# jn5189_pcb_v1.net
KiCad netlist of a schematic drawn in EAGLE
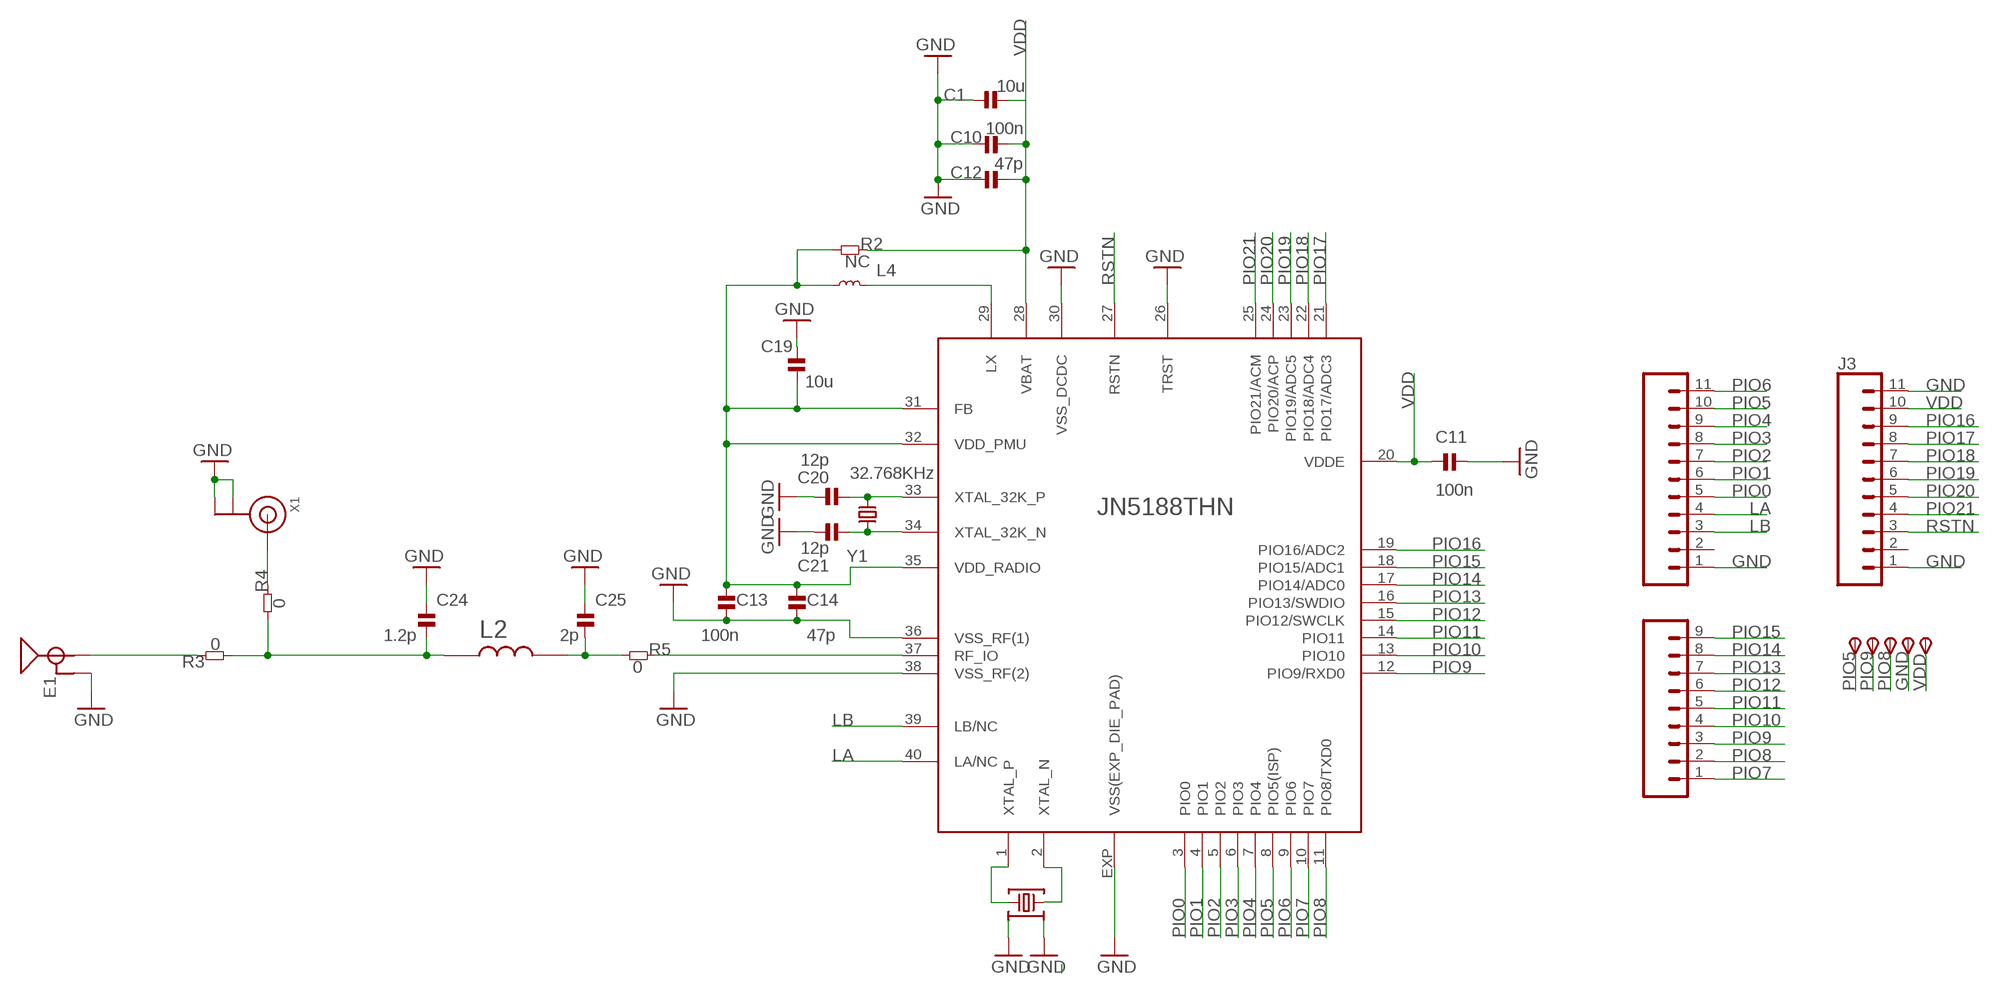
[diagram p0: schematic, sheet 1]

(export (version "E")
  (design (tool "Eeschema 10.0.6"))
  (components
    (comp (ref "3V3")
      (value "TPSTP11R")
      (footprint "eagle-import:TP11R")
      (libsource (lib "eagle-import") (part "TPSTP11R"))
    )
    (comp (ref "C1")
      (value "10u")
      (footprint "eagle-import:_PKG_C_0805")
      (libsource (lib "eagle-import") (part "CAP-0805"))
    )
    (comp (ref "C10")
      (value "100n")
      (footprint "eagle-import:_PKG_C_0402")
      (libsource (lib "eagle-import") (part "CAP-0402"))
    )
    (comp (ref "C11")
      (value "100n")
      (footprint "eagle-import:_PKG_C_0402")
      (libsource (lib "eagle-import") (part "CAP-0402"))
    )
    (comp (ref "C12")
      (value "47p")
      (footprint "eagle-import:_PKG_C_0402")
      (libsource (lib "eagle-import") (part "CAP-0402"))
    )
    (comp (ref "C13")
      (value "100n")
      (footprint "eagle-import:_PKG_C_0402")
      (libsource (lib "eagle-import") (part "CAP-0402"))
    )
    (comp (ref "C14")
      (value "47p")
      (footprint "eagle-import:_PKG_C_0402")
      (libsource (lib "eagle-import") (part "CAP-0402"))
    )
    (comp (ref "C19")
      (value "10u")
      (footprint "eagle-import:_PKG_C_0805")
      (libsource (lib "eagle-import") (part "CAP-0805"))
    )
    (comp (ref "C20")
      (value "12p")
      (footprint "eagle-import:_PKG_C_0402")
      (libsource (lib "eagle-import") (part "CAP-0402"))
    )
    (comp (ref "C21")
      (value "12p")
      (footprint "eagle-import:_PKG_C_0402")
      (libsource (lib "eagle-import") (part "CAP-0402"))
    )
    (comp (ref "C24")
      (value "1.2p")
      (footprint "eagle-import:_PKG_C_0402")
      (libsource (lib "eagle-import") (part "CAP-0402"))
    )
    (comp (ref "C25")
      (value "2p")
      (footprint "eagle-import:_PKG_C_0402")
      (libsource (lib "eagle-import") (part "CAP-0402"))
    )
    (comp (ref "E1")
      (value "ANTENNA-GROUNDEDTRACE-15.2MM")
      (footprint "eagle-import:TRACE_ANTENNA_2.4GHZ_15.2MM")
      (libsource (lib "eagle-import") (part "ANTENNA-GROUNDEDTRACE-15.2MM"))
    )
    (comp (ref "GND")
      (value "TPSTP11R")
      (footprint "eagle-import:TP11R")
      (libsource (lib "eagle-import") (part "TPSTP11R"))
    )
    (comp (ref "ISP")
      (value "TPSTP11R")
      (footprint "eagle-import:TP11R")
      (libsource (lib "eagle-import") (part "TPSTP11R"))
    )
    (comp (ref "J1")
      (value "CONN_11_1.27MM")
      (footprint "eagle-import:1X11-1.27MM")
      (libsource (lib "eagle-import") (part "CONN_11_1.27MM"))
    )
    (comp (ref "J2")
      (value "CONN_051.27MM")
      (footprint "eagle-import:1X05_1.27MM")
      (libsource (lib "eagle-import") (part "CONN_051.27MM"))
    )
    (comp (ref "J3")
      (value "CONN_11_1.27MM")
      (footprint "eagle-import:1X11-1.27MM")
      (libsource (lib "eagle-import") (part "CONN_11_1.27MM"))
    )
    (comp (ref "L2")
      (value "3.3n")
      (footprint "eagle-import:INDC1005X40N")
      (fields (field (name "MF") "Yageo") (field (name "MP") "RC0402FR-073M6L"))
      (libsource (lib "eagle-import") (part "IND0402IND0402"))
    )
    (comp (ref "L4")
      (value "4.7uH")
      (footprint "eagle-import:_PKG_C_0805")
      (libsource (lib "eagle-import") (part "INDUCTOR-0805"))
    )
    (comp (ref "R2")
      (value "NC")
      (footprint "eagle-import:_PKG_C_0402")
      (libsource (lib "eagle-import") (part "RES-0402"))
    )
    (comp (ref "R3")
      (value "0")
      (footprint "eagle-import:_PKG_C_0402")
      (libsource (lib "eagle-import") (part "RES-0402"))
    )
    (comp (ref "R4")
      (value "0")
      (footprint "eagle-import:_PKG_C_0402")
      (libsource (lib "eagle-import") (part "RES-0402"))
    )
    (comp (ref "R5")
      (value "0")
      (footprint "eagle-import:_PKG_C_0402")
      (libsource (lib "eagle-import") (part "RES-0402"))
    )
    (comp (ref "RXD")
      (value "TPSTP11R")
      (footprint "eagle-import:TP11R")
      (libsource (lib "eagle-import") (part "TPSTP11R"))
    )
    (comp (ref "TXD")
      (value "TPSTP11R")
      (footprint "eagle-import:TP11R")
      (libsource (lib "eagle-import") (part "TPSTP11R"))
    )
    (comp (ref "U$1")
      (value "JN5188THN")
      (footprint "eagle-import:JN5188THN")
      (fields (field (name "MF") "NXP Semiconductors") (field (name "MP") "JN5168/A02Z"))
      (libsource (lib "eagle-import") (part "JN5188THN"))
    )
    (comp (ref "X1")
      (value "ANTENNA_U.FL")
      (footprint "eagle-import:U.FL")
      (libsource (lib "eagle-import") (part "ANTENNA_U.FL"))
    )
    (comp (ref "Y1")
      (value "32.768KHz")
      (footprint "eagle-import:XTAL-2P-3215")
      (fields (field (name "LCSC_PART") "C32346") (field (name "MFG_PART") "Q13FC1350000400"))
      (libsource (lib "eagle-import") (part "32.768KHZ_Q13FC1350000400"))
    )
    (comp (ref "Y2")
      (value "32Mhz")
      (footprint "eagle-import:XTAL-4P-2016")
      (fields (field (name "DIGIKEY_PART") "1253-2042-1-ND") (field (name "MFG_PART") "CX2016DB48000C0FPLC1"))
      (libsource (lib "eagle-import") (part "48.000MHZ_CX2016DB48000C0FPLC1"))
    )
  )
  (nets
    (net (code "1") (name "/LA") (class "Default")
      (node (ref "J1") (pin "4") (pinfunction "4_4") (pintype "passive"))
      (node (ref "U$1") (pin "40") (pinfunction "LA/NC_40") (pintype "bidirectional"))
    )
    (net (code "2") (name "/LB") (class "Default")
      (node (ref "J1") (pin "3") (pinfunction "3_3") (pintype "passive"))
      (node (ref "U$1") (pin "39") (pinfunction "LB/NC_39") (pintype "bidirectional"))
    )
    (net (code "3") (name "/PIO0") (class "Default")
      (node (ref "J1") (pin "5") (pinfunction "5_5") (pintype "passive"))
      (node (ref "U$1") (pin "3") (pinfunction "PIO0_3") (pintype "bidirectional"))
    )
    (net (code "4") (name "/PIO1") (class "Default")
      (node (ref "J1") (pin "6") (pinfunction "6_6") (pintype "passive"))
      (node (ref "U$1") (pin "4") (pinfunction "PIO1_4") (pintype "bidirectional"))
    )
    (net (code "5") (name "/PIO2") (class "Default")
      (node (ref "J1") (pin "7") (pinfunction "7_7") (pintype "passive"))
      (node (ref "U$1") (pin "5") (pinfunction "PIO2_5") (pintype "bidirectional"))
    )
    (net (code "6") (name "/PIO3") (class "Default")
      (node (ref "J1") (pin "8") (pinfunction "8_8") (pintype "passive"))
      (node (ref "U$1") (pin "6") (pinfunction "PIO3_6") (pintype "bidirectional"))
    )
    (net (code "7") (name "/PIO4") (class "Default")
      (node (ref "J1") (pin "9") (pinfunction "9_9") (pintype "passive"))
      (node (ref "U$1") (pin "7") (pinfunction "PIO4_7") (pintype "bidirectional"))
    )
    (net (code "8") (name "/PIO5") (class "Default")
      (node (ref "ISP") (pin "TP") (pinfunction "PP_TP") (pintype "input"))
      (node (ref "J1") (pin "10") (pinfunction "10_10") (pintype "passive"))
      (node (ref "U$1") (pin "8") (pinfunction "PIO5(ISP)_8") (pintype "bidirectional"))
    )
    (net (code "9") (name "/PIO6") (class "Default")
      (node (ref "J1") (pin "11") (pinfunction "11_11") (pintype "passive"))
      (node (ref "U$1") (pin "9") (pinfunction "PIO6_9") (pintype "bidirectional"))
    )
    (net (code "10") (name "/PIO7") (class "Default")
      (node (ref "J2") (pin "1") (pinfunction "1_1") (pintype "passive"))
      (node (ref "U$1") (pin "10") (pinfunction "PIO7_10") (pintype "bidirectional"))
    )
    (net (code "11") (name "/PIO8") (class "Default")
      (node (ref "J2") (pin "2") (pinfunction "2_2") (pintype "passive"))
      (node (ref "TXD") (pin "TP") (pinfunction "PP_TP") (pintype "input"))
      (node (ref "U$1") (pin "11") (pinfunction "PIO8/TXD0_11") (pintype "bidirectional"))
    )
    (net (code "12") (name "/PIO9") (class "Default")
      (node (ref "J2") (pin "3") (pinfunction "3_3") (pintype "passive"))
      (node (ref "RXD") (pin "TP") (pinfunction "PP_TP") (pintype "input"))
      (node (ref "U$1") (pin "12") (pinfunction "PIO9/RXD0_12") (pintype "bidirectional"))
    )
    (net (code "13") (name "/PIO10") (class "Default")
      (node (ref "J2") (pin "4") (pinfunction "4_4") (pintype "passive"))
      (node (ref "U$1") (pin "13") (pinfunction "PIO10_13") (pintype "bidirectional"))
    )
    (net (code "14") (name "/PIO11") (class "Default")
      (node (ref "J2") (pin "5") (pinfunction "5_5") (pintype "passive"))
      (node (ref "U$1") (pin "14") (pinfunction "PIO11_14") (pintype "bidirectional"))
    )
    (net (code "15") (name "/PIO12") (class "Default")
      (node (ref "J2") (pin "6") (pinfunction "6_6") (pintype "passive"))
      (node (ref "U$1") (pin "15") (pinfunction "PIO12/SWCLK_15") (pintype "bidirectional"))
    )
    (net (code "16") (name "/PIO13") (class "Default")
      (node (ref "J2") (pin "7") (pinfunction "7_7") (pintype "passive"))
      (node (ref "U$1") (pin "16") (pinfunction "PIO13/SWDIO_16") (pintype "bidirectional"))
    )
    (net (code "17") (name "/PIO14") (class "Default")
      (node (ref "J2") (pin "8") (pinfunction "8_8") (pintype "passive"))
      (node (ref "U$1") (pin "17") (pinfunction "PIO14/ADC0_17") (pintype "bidirectional"))
    )
    (net (code "18") (name "/PIO15") (class "Default")
      (node (ref "J2") (pin "9") (pinfunction "9_9") (pintype "passive"))
      (node (ref "U$1") (pin "18") (pinfunction "PIO15/ADC1_18") (pintype "bidirectional"))
    )
    (net (code "19") (name "/PIO16") (class "Default")
      (node (ref "J3") (pin "9") (pinfunction "9_9") (pintype "passive"))
      (node (ref "U$1") (pin "19") (pinfunction "PIO16/ADC2_19") (pintype "bidirectional"))
    )
    (net (code "20") (name "/PIO17") (class "Default")
      (node (ref "J3") (pin "8") (pinfunction "8_8") (pintype "passive"))
      (node (ref "U$1") (pin "21") (pinfunction "PIO17/ADC3_21") (pintype "bidirectional"))
    )
    (net (code "21") (name "/PIO18") (class "Default")
      (node (ref "J3") (pin "7") (pinfunction "7_7") (pintype "passive"))
      (node (ref "U$1") (pin "22") (pinfunction "PIO18/ADC4_22") (pintype "bidirectional"))
    )
    (net (code "22") (name "/PIO19") (class "Default")
      (node (ref "J3") (pin "6") (pinfunction "6_6") (pintype "passive"))
      (node (ref "U$1") (pin "23") (pinfunction "PIO19/ADC5_23") (pintype "bidirectional"))
    )
    (net (code "23") (name "/PIO20") (class "Default")
      (node (ref "J3") (pin "5") (pinfunction "5_5") (pintype "passive"))
      (node (ref "U$1") (pin "24") (pinfunction "PIO20/ACP_24") (pintype "bidirectional"))
    )
    (net (code "24") (name "/PIO21") (class "Default")
      (node (ref "J3") (pin "4") (pinfunction "4_4") (pintype "passive"))
      (node (ref "U$1") (pin "25") (pinfunction "PIO21/ACM_25") (pintype "bidirectional"))
    )
    (net (code "25") (name "/RSTN") (class "Default")
      (node (ref "J3") (pin "3") (pinfunction "3_3") (pintype "passive"))
      (node (ref "U$1") (pin "27") (pinfunction "RSTN_27") (pintype "bidirectional"))
    )
    (net (code "26") (name "/VDD") (class "Default")
      (node (ref "3V3") (pin "TP") (pinfunction "PP_TP") (pintype "input"))
      (node (ref "C1") (pin "2") (pinfunction "2_2") (pintype "passive"))
      (node (ref "C10") (pin "1") (pinfunction "1_1") (pintype "passive"))
      (node (ref "C11") (pin "2") (pinfunction "2_2") (pintype "passive"))
      (node (ref "C12") (pin "1") (pinfunction "1_1") (pintype "passive"))
      (node (ref "J3") (pin "10") (pinfunction "10_10") (pintype "passive"))
      (node (ref "R2") (pin "1") (pinfunction "1_1") (pintype "passive"))
      (node (ref "U$1") (pin "20") (pinfunction "VDDE_20") (pintype "bidirectional"))
      (node (ref "U$1") (pin "28") (pinfunction "VBAT_28") (pintype "bidirectional"))
    )
    (net (code "27") (name "GND") (class "Default")
      (node (ref "C1") (pin "1") (pinfunction "1_1") (pintype "passive"))
      (node (ref "C10") (pin "2") (pinfunction "2_2") (pintype "passive"))
      (node (ref "C11") (pin "1") (pinfunction "1_1") (pintype "passive"))
      (node (ref "C12") (pin "2") (pinfunction "2_2") (pintype "passive"))
      (node (ref "C13") (pin "1") (pinfunction "1_1") (pintype "passive"))
      (node (ref "C14") (pin "1") (pinfunction "1_1") (pintype "passive"))
      (node (ref "C19") (pin "1") (pinfunction "1_1") (pintype "passive"))
      (node (ref "C20") (pin "1") (pinfunction "1_1") (pintype "passive"))
      (node (ref "C21") (pin "1") (pinfunction "1_1") (pintype "passive"))
      (node (ref "C24") (pin "2") (pinfunction "2_2") (pintype "passive"))
      (node (ref "C25") (pin "2") (pinfunction "2_2") (pintype "passive"))
      (node (ref "E1") (pin "GND") (pinfunction "GND_GND") (pintype "bidirectional"))
      (node (ref "GND") (pin "TP") (pinfunction "PP_TP") (pintype "input"))
      (node (ref "J1") (pin "1") (pinfunction "1_1") (pintype "passive"))
      (node (ref "J3") (pin "1") (pinfunction "1_1") (pintype "passive"))
      (node (ref "J3") (pin "11") (pinfunction "11_11") (pintype "passive"))
      (node (ref "U$1") (pin "26") (pinfunction "TRST_26") (pintype "bidirectional"))
      (node (ref "U$1") (pin "30") (pinfunction "VSS_DCDC_30") (pintype "bidirectional"))
      (node (ref "U$1") (pin "36") (pinfunction "VSS_RF(1)_36") (pintype "bidirectional"))
      (node (ref "U$1") (pin "38") (pinfunction "VSS_RF(2)_38") (pintype "bidirectional"))
      (node (ref "U$1") (pin "EXP") (pinfunction "VSS(EXP_DIE_PAD)_EXP") (pintype "bidirectional"))
      (node (ref "X1") (pin "1") (pinfunction "GND_1") (pintype "passive"))
      (node (ref "X1") (pin "2") (pinfunction "GND_2") (pintype "passive"))
      (node (ref "Y2") (pin "2") (pinfunction "2_2") (pintype "bidirectional"))
      (node (ref "Y2") (pin "4") (pinfunction "4_4") (pintype "bidirectional"))
    )
    (net (code "28") (name "Net-(C24-Pad1)") (class "Default")
      (node (ref "C24") (pin "1") (pinfunction "1_1") (pintype "passive"))
      (node (ref "L2") (pin "1") (pinfunction "1_1") (pintype "passive"))
      (node (ref "R3") (pin "2") (pinfunction "2_2") (pintype "passive"))
      (node (ref "R4") (pin "2") (pinfunction "2_2") (pintype "passive"))
    )
    (net (code "29") (name "Net-(C25-Pad1)") (class "Default")
      (node (ref "C25") (pin "1") (pinfunction "1_1") (pintype "passive"))
      (node (ref "L2") (pin "2") (pinfunction "2_2") (pintype "passive"))
      (node (ref "R5") (pin "2") (pinfunction "2_2") (pintype "passive"))
    )
    (net (code "30") (name "Net-(E1-SIGNAL)") (class "Default")
      (node (ref "E1") (pin "ANT") (pinfunction "SIGNAL_ANT") (pintype "bidirectional"))
      (node (ref "R3") (pin "1") (pinfunction "1_1") (pintype "passive"))
    )
    (net (code "31") (name "Net-(U$1-FB)") (class "Default")
      (node (ref "C13") (pin "2") (pinfunction "2_2") (pintype "passive"))
      (node (ref "C14") (pin "2") (pinfunction "2_2") (pintype "passive"))
      (node (ref "C19") (pin "2") (pinfunction "2_2") (pintype "passive"))
      (node (ref "L4") (pin "1") (pinfunction "1_1") (pintype "passive"))
      (node (ref "R2") (pin "2") (pinfunction "2_2") (pintype "passive"))
      (node (ref "U$1") (pin "31") (pinfunction "FB_31") (pintype "bidirectional"))
      (node (ref "U$1") (pin "32") (pinfunction "VDD_PMU_32") (pintype "bidirectional"))
      (node (ref "U$1") (pin "35") (pinfunction "VDD_RADIO_35") (pintype "bidirectional"))
    )
    (net (code "32") (name "Net-(U$1-LX)") (class "Default")
      (node (ref "L4") (pin "2") (pinfunction "2_2") (pintype "passive"))
      (node (ref "U$1") (pin "29") (pinfunction "LX_29") (pintype "bidirectional"))
    )
    (net (code "33") (name "Net-(U$1-RF_IO)") (class "Default")
      (node (ref "R5") (pin "1") (pinfunction "1_1") (pintype "passive"))
      (node (ref "U$1") (pin "37") (pinfunction "RF_IO_37") (pintype "bidirectional"))
    )
    (net (code "34") (name "Net-(U$1-XTAL_32K_N)") (class "Default")
      (node (ref "C21") (pin "2") (pinfunction "2_2") (pintype "passive"))
      (node (ref "U$1") (pin "34") (pinfunction "XTAL_32K_N_34") (pintype "bidirectional"))
      (node (ref "Y1") (pin "2") (pinfunction "2_2") (pintype "passive"))
    )
    (net (code "35") (name "Net-(U$1-XTAL_32K_P)") (class "Default")
      (node (ref "C20") (pin "2") (pinfunction "2_2") (pintype "passive"))
      (node (ref "U$1") (pin "33") (pinfunction "XTAL_32K_P_33") (pintype "bidirectional"))
      (node (ref "Y1") (pin "1") (pinfunction "1_1") (pintype "passive"))
    )
    (net (code "36") (name "Net-(U$1-XTAL_N)") (class "Default")
      (node (ref "U$1") (pin "2") (pinfunction "XTAL_N_2") (pintype "bidirectional"))
      (node (ref "Y2") (pin "3") (pinfunction "3_3") (pintype "passive"))
    )
    (net (code "37") (name "Net-(U$1-XTAL_P)") (class "Default")
      (node (ref "U$1") (pin "1") (pinfunction "XTAL_P_1") (pintype "bidirectional"))
      (node (ref "Y2") (pin "1") (pinfunction "1_1") (pintype "passive"))
    )
    (net (code "38") (name "Net-(X1-SIGNAL)") (class "Default")
      (node (ref "R4") (pin "1") (pinfunction "1_1") (pintype "passive"))
      (node (ref "X1") (pin "3") (pinfunction "SIGNAL_3") (pintype "passive"))
    )
    (net (code "39") (name "unconnected-(J1-Pad2)") (class "Default")
      (node (ref "J1") (pin "2") (pinfunction "2_2") (pintype "passive"))
    )
    (net (code "40") (name "unconnected-(J3-Pad2)") (class "Default")
      (node (ref "J3") (pin "2") (pinfunction "2_2") (pintype "passive"))
    )
  )
)
